# Hexagonal_MCU_V02.net
KiCad netlist of a schematic drawn in EAGLE
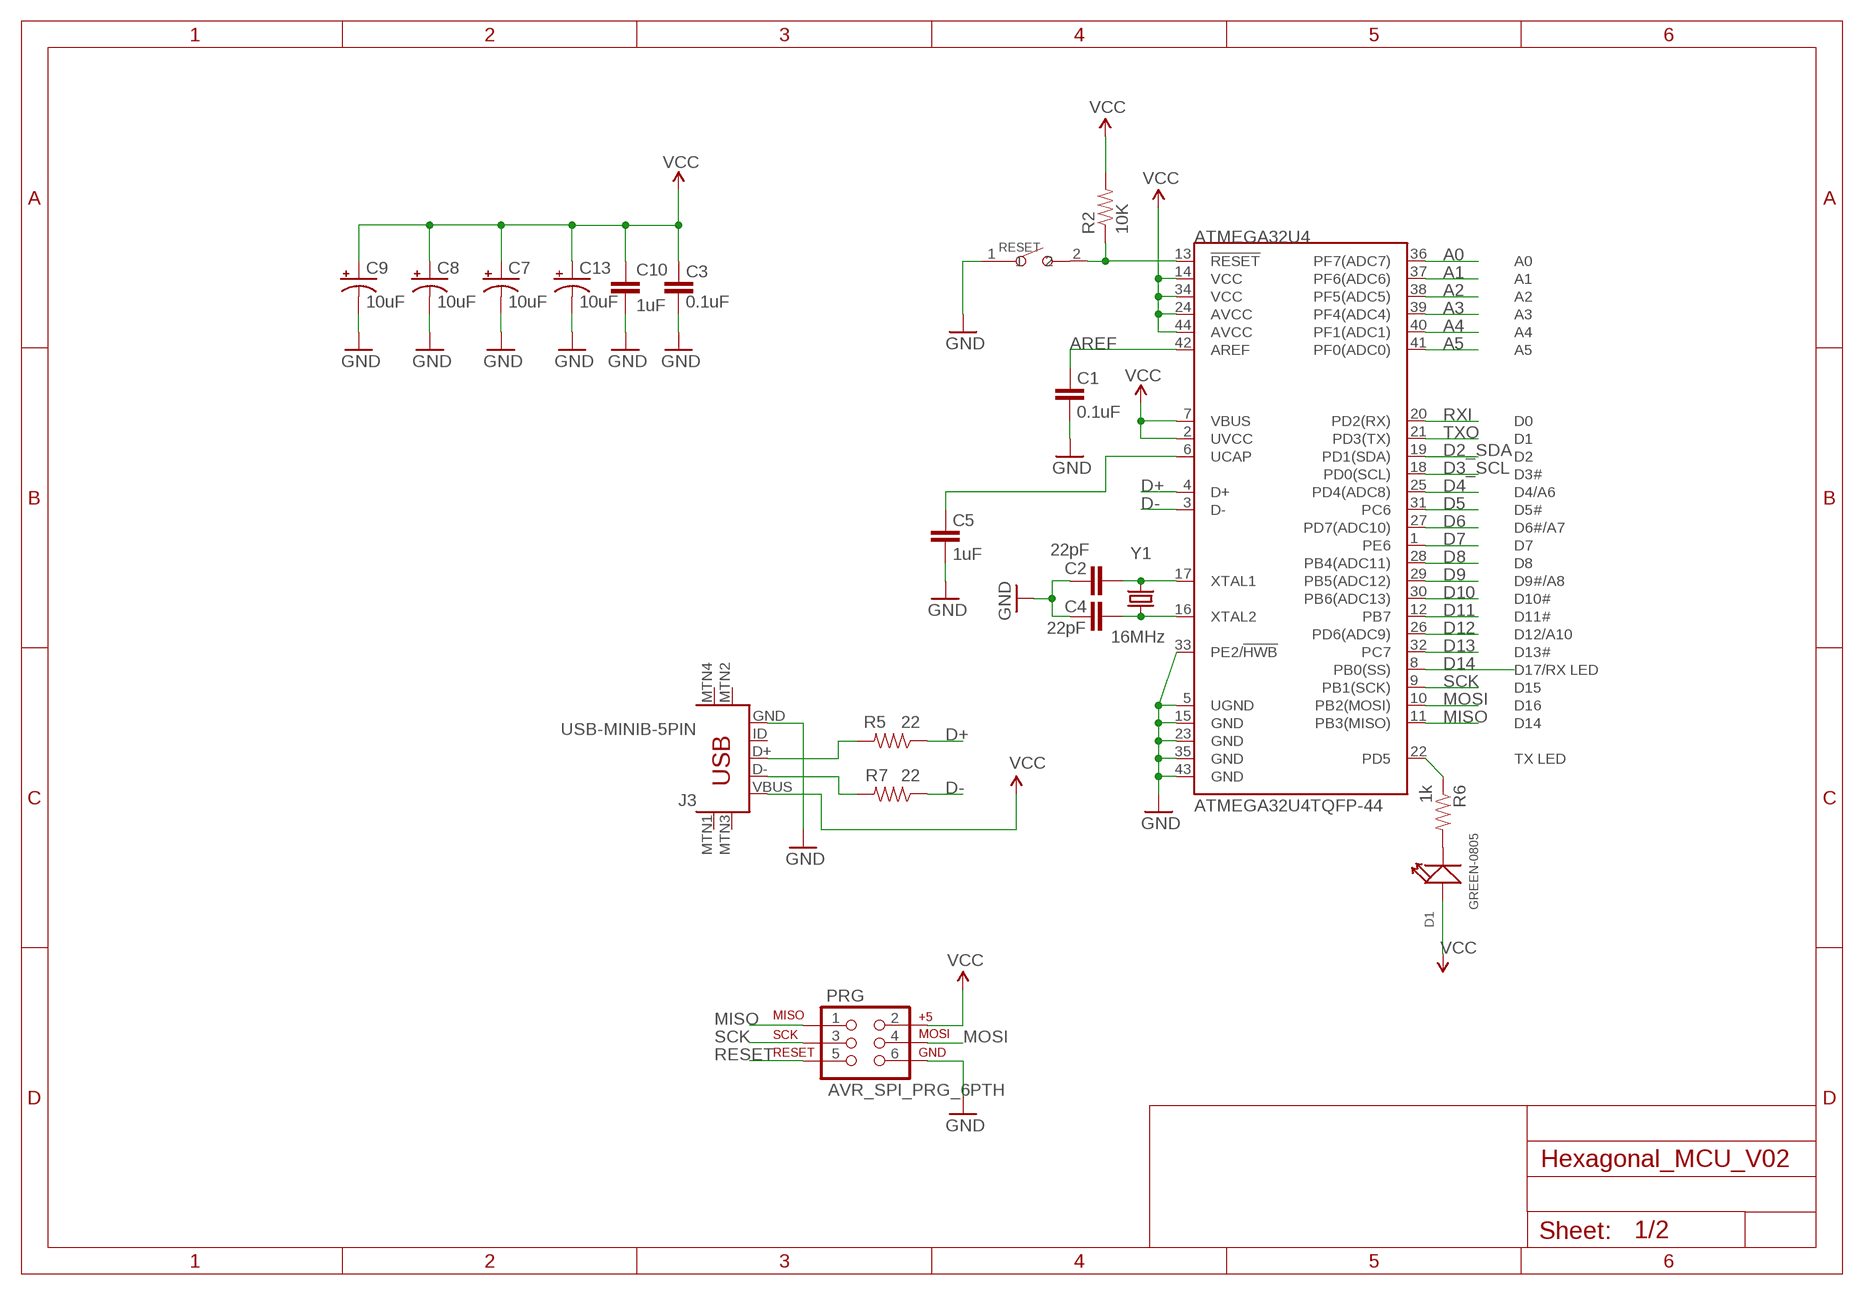
[diagram p0: schematic, sheet 1]
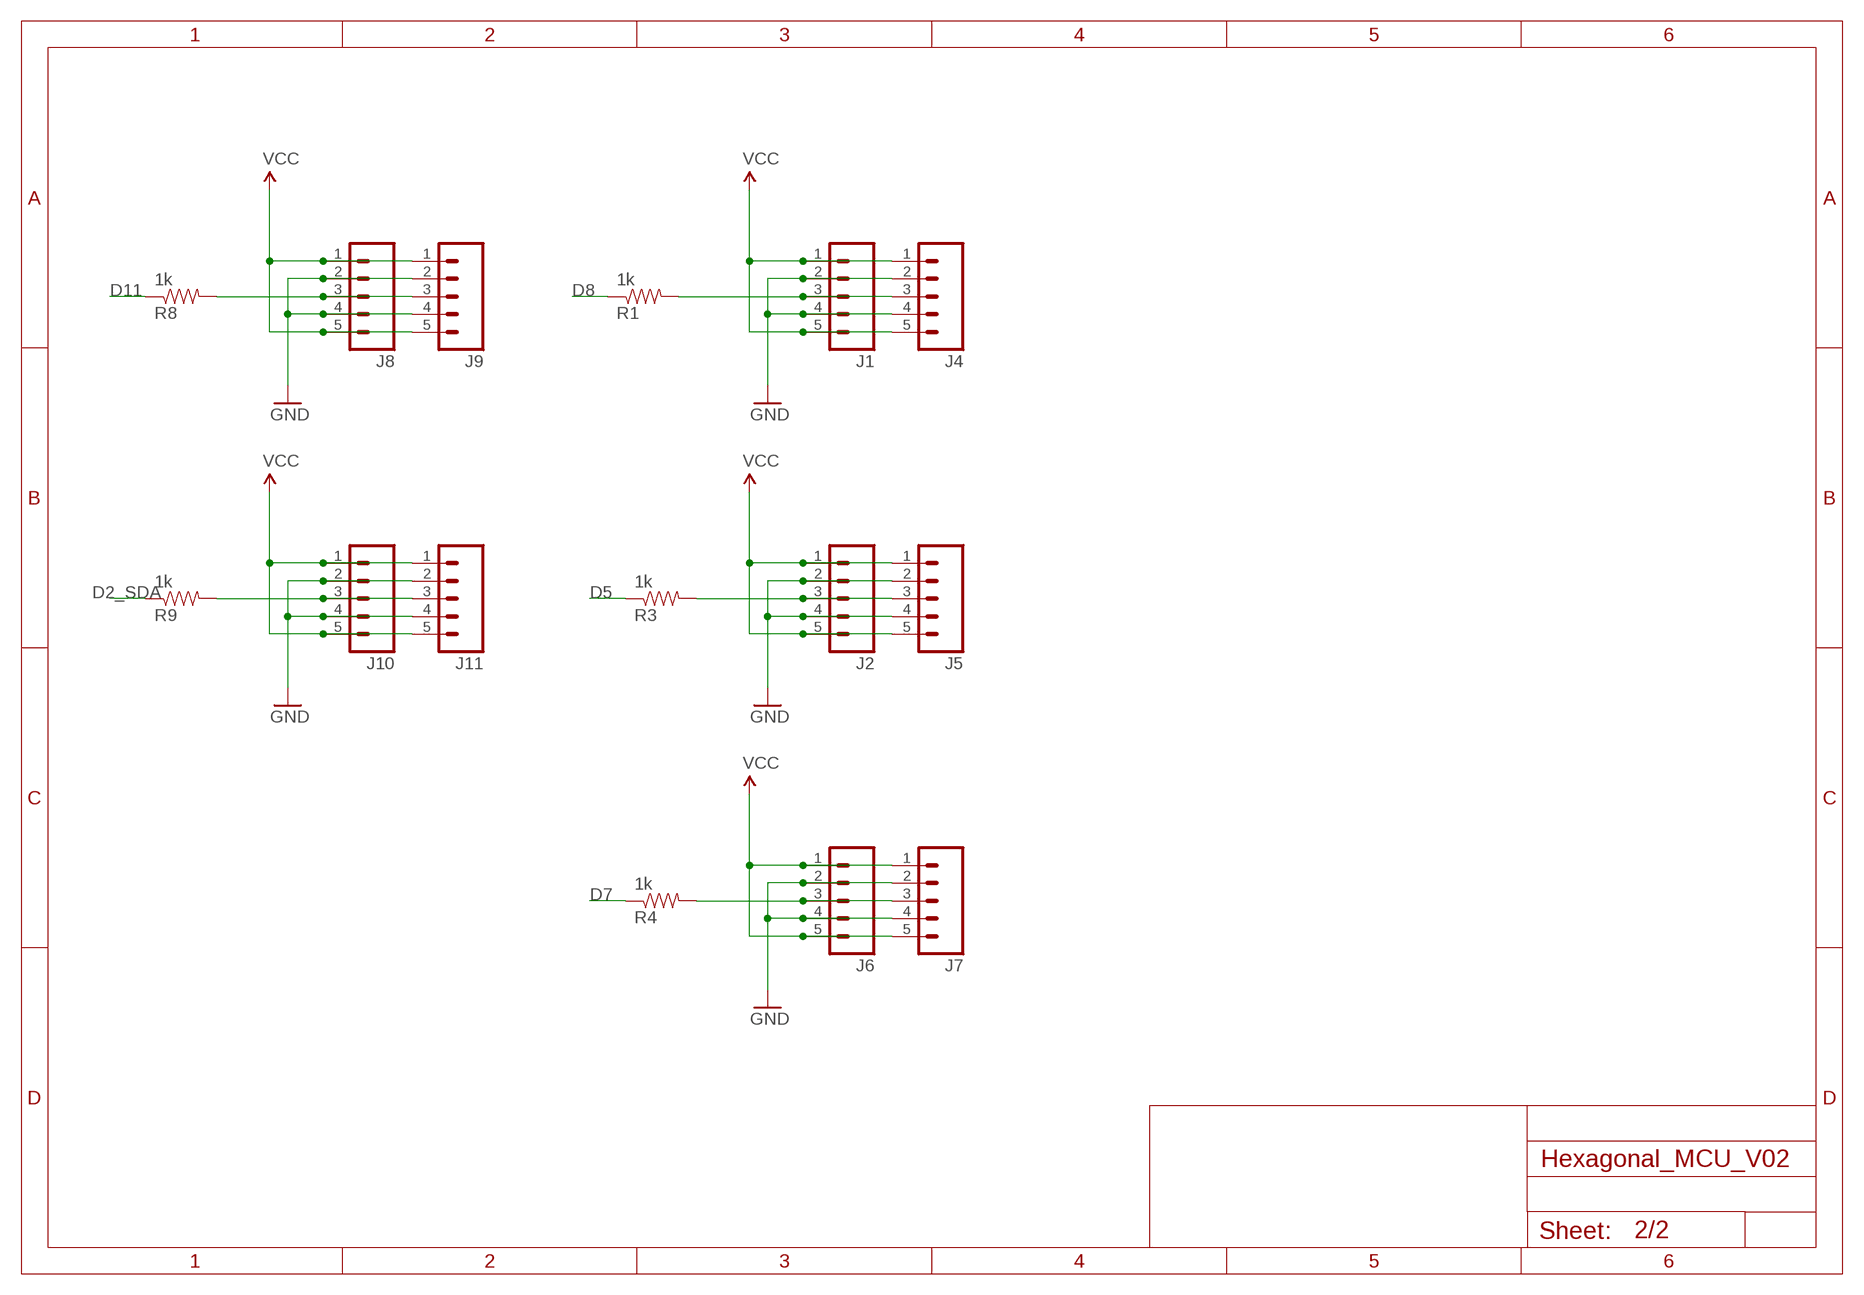
[diagram p1: schematic, sheet 2]

(export (version "E")
  (design (tool "Eeschema 10.0.6"))
  (components
    (comp (ref "ATMEGA32U4")
      (value "ATMEGA32U4TQFP-44")
      (footprint "eagle-import:TQFP44")
      (libsource (lib "eagle-import") (part "ATMEGA32U4TQFP-44"))
    )
    (comp (ref "C1")
      (value "0.1uF")
      (footprint "eagle-import:0805")
      (libsource (lib "eagle-import") (part "CAP0805"))
    )
    (comp (ref "C2")
      (value "22pF")
      (footprint "eagle-import:0805")
      (libsource (lib "eagle-import") (part "CAP0805"))
    )
    (comp (ref "C3")
      (value "0.1uF")
      (footprint "eagle-import:0805")
      (libsource (lib "eagle-import") (part "CAP0805"))
    )
    (comp (ref "C4")
      (value "22pF")
      (footprint "eagle-import:0805")
      (libsource (lib "eagle-import") (part "CAP0805"))
    )
    (comp (ref "C5")
      (value "1uF")
      (footprint "eagle-import:0805")
      (libsource (lib "eagle-import") (part "CAP0805"))
    )
    (comp (ref "C7")
      (value "10uF")
      (footprint "eagle-import:EIA3216")
      (libsource (lib "eagle-import") (part "CAP_POL1206"))
    )
    (comp (ref "C8")
      (value "10uF")
      (footprint "eagle-import:EIA3216")
      (libsource (lib "eagle-import") (part "CAP_POL1206"))
    )
    (comp (ref "C9")
      (value "10uF")
      (footprint "eagle-import:EIA3216")
      (libsource (lib "eagle-import") (part "CAP_POL1206"))
    )
    (comp (ref "C10")
      (value "1uF")
      (footprint "eagle-import:0805")
      (libsource (lib "eagle-import") (part "CAP0805"))
    )
    (comp (ref "C13")
      (value "10uF")
      (footprint "eagle-import:EIA3216")
      (libsource (lib "eagle-import") (part "CAP_POL1206"))
    )
    (comp (ref "D1")
      (value "GREEN-0805")
      (footprint "eagle-import:LED-0805")
      (fields (field (name "MPN") "17-215SYGC/S530-E2/TR8"))
      (libsource (lib "eagle-import") (part "SMD-LED-CLEAR-GREEN(0805)"))
    )
    (comp (ref "J3")
      (value "USB-MINIB-5PIN")
      (footprint "eagle-import:USB-MINIB")
      (libsource (lib "eagle-import") (part "USB-MINIB-5PIN"))
    )
    (comp (ref "PRG")
      (value "AVR_SPI_PRG_6PTH")
      (footprint "eagle-import:2X3")
      (libsource (lib "eagle-import") (part "AVR_SPI_PRG_6PTH"))
    )
    (comp (ref "R2")
      (value "10K")
      (footprint "eagle-import:0805")
      (libsource (lib "eagle-import") (part "RESISTOR0805-RES"))
    )
    (comp (ref "R5")
      (value "22")
      (footprint "eagle-import:0805")
      (libsource (lib "eagle-import") (part "RESISTOR0805-RES"))
    )
    (comp (ref "R6")
      (value "1k")
      (footprint "eagle-import:0805")
      (libsource (lib "eagle-import") (part "RESISTOR0805-RES"))
    )
    (comp (ref "R7")
      (value "22")
      (footprint "eagle-import:0805")
      (libsource (lib "eagle-import") (part "RESISTOR0805-RES"))
    )
    (comp (ref "RESET")
      (value "B3U-1000P-2P-SMD")
      (footprint "eagle-import:SW2-4.0X3.0X2.0")
      (libsource (lib "eagle-import") (part "SMD-BUTTON(2P-4.0X3.0X1.5+0.5MM)SW-TS-017A-2P"))
    )
    (comp (ref "Y1")
      (value "16MHz")
      (footprint "eagle-import:HC49US")
      (libsource (lib "eagle-import") (part "CRYSTALHC49US"))
    )
    (comp (ref "J1")
      (value "M05NO_SILK")
      (footprint "eagle-import:1X05_NO_SILK")
      (libsource (lib "eagle-import") (part "M05NO_SILK"))
    )
    (comp (ref "J2")
      (value "M05NO_SILK")
      (footprint "eagle-import:1X05_NO_SILK")
      (libsource (lib "eagle-import") (part "M05NO_SILK"))
    )
    (comp (ref "J4")
      (value "M05PTH_LONGPADS")
      (footprint "eagle-import:1X05_LONGPADS")
      (libsource (lib "eagle-import") (part "M05PTH_LONGPADS"))
    )
    (comp (ref "J5")
      (value "M05PTH_LONGPADS")
      (footprint "eagle-import:1X05_LONGPADS")
      (libsource (lib "eagle-import") (part "M05PTH_LONGPADS"))
    )
    (comp (ref "J6")
      (value "M05NO_SILK")
      (footprint "eagle-import:1X05_NO_SILK")
      (libsource (lib "eagle-import") (part "M05NO_SILK"))
    )
    (comp (ref "J7")
      (value "M05PTH_LONGPADS")
      (footprint "eagle-import:1X05_LONGPADS")
      (libsource (lib "eagle-import") (part "M05PTH_LONGPADS"))
    )
    (comp (ref "J8")
      (value "M05NO_SILK")
      (footprint "eagle-import:1X05_NO_SILK")
      (libsource (lib "eagle-import") (part "M05NO_SILK"))
    )
    (comp (ref "J9")
      (value "M05PTH_LONGPADS")
      (footprint "eagle-import:1X05_LONGPADS")
      (libsource (lib "eagle-import") (part "M05PTH_LONGPADS"))
    )
    (comp (ref "J10")
      (value "M05NO_SILK")
      (footprint "eagle-import:1X05_NO_SILK")
      (libsource (lib "eagle-import") (part "M05NO_SILK"))
    )
    (comp (ref "J11")
      (value "M05PTH_LONGPADS")
      (footprint "eagle-import:1X05_LONGPADS")
      (libsource (lib "eagle-import") (part "M05PTH_LONGPADS"))
    )
    (comp (ref "R1")
      (value "1k")
      (footprint "eagle-import:0805")
      (libsource (lib "eagle-import") (part "RESISTOR0805-RES"))
    )
    (comp (ref "R3")
      (value "1k")
      (footprint "eagle-import:0805")
      (libsource (lib "eagle-import") (part "RESISTOR0805-RES"))
    )
    (comp (ref "R4")
      (value "1k")
      (footprint "eagle-import:0805")
      (libsource (lib "eagle-import") (part "RESISTOR0805-RES"))
    )
    (comp (ref "R8")
      (value "1k")
      (footprint "eagle-import:0805")
      (libsource (lib "eagle-import") (part "RESISTOR0805-RES"))
    )
    (comp (ref "R9")
      (value "1k")
      (footprint "eagle-import:0805")
      (libsource (lib "eagle-import") (part "RESISTOR0805-RES"))
    )
  )
  (nets
    (net (code "1") (name "5V") (class "Default")
      (node (ref "ATMEGA32U4") (pin "14") (pinfunction "VCC_14") (pintype "bidirectional"))
      (node (ref "ATMEGA32U4") (pin "2") (pinfunction "UVCC_2") (pintype "bidirectional"))
      (node (ref "ATMEGA32U4") (pin "24") (pinfunction "AVCC_24") (pintype "bidirectional"))
      (node (ref "ATMEGA32U4") (pin "34") (pinfunction "VCC_34") (pintype "bidirectional"))
      (node (ref "ATMEGA32U4") (pin "44") (pinfunction "AVCC_44") (pintype "bidirectional"))
      (node (ref "ATMEGA32U4") (pin "7") (pinfunction "VBUS_7") (pintype "bidirectional"))
      (node (ref "C10") (pin "1") (pinfunction "1_1") (pintype "passive"))
      (node (ref "C13") (pin "A") (pinfunction "+_A") (pintype "passive"))
      (node (ref "C3") (pin "2") (pinfunction "2_2") (pintype "passive"))
      (node (ref "C7") (pin "A") (pinfunction "+_A") (pintype "passive"))
      (node (ref "C8") (pin "A") (pinfunction "+_A") (pintype "passive"))
      (node (ref "C9") (pin "A") (pinfunction "+_A") (pintype "passive"))
      (node (ref "D1") (pin "+") (pinfunction "+_+") (pintype "passive"))
      (node (ref "J1") (pin "1") (pinfunction "1_1") (pintype "passive"))
      (node (ref "J1") (pin "5") (pinfunction "5_5") (pintype "passive"))
      (node (ref "J10") (pin "1") (pinfunction "1_1") (pintype "passive"))
      (node (ref "J10") (pin "5") (pinfunction "5_5") (pintype "passive"))
      (node (ref "J11") (pin "1") (pinfunction "1_1") (pintype "passive"))
      (node (ref "J11") (pin "5") (pinfunction "5_5") (pintype "passive"))
      (node (ref "J2") (pin "1") (pinfunction "1_1") (pintype "passive"))
      (node (ref "J2") (pin "5") (pinfunction "5_5") (pintype "passive"))
      (node (ref "J3") (pin "VBUS") (pinfunction "VBUS_VBUS") (pintype "bidirectional"))
      (node (ref "J4") (pin "1") (pinfunction "1_1") (pintype "passive"))
      (node (ref "J4") (pin "5") (pinfunction "5_5") (pintype "passive"))
      (node (ref "J5") (pin "1") (pinfunction "1_1") (pintype "passive"))
      (node (ref "J5") (pin "5") (pinfunction "5_5") (pintype "passive"))
      (node (ref "J6") (pin "1") (pinfunction "1_1") (pintype "passive"))
      (node (ref "J6") (pin "5") (pinfunction "5_5") (pintype "passive"))
      (node (ref "J7") (pin "1") (pinfunction "1_1") (pintype "passive"))
      (node (ref "J7") (pin "5") (pinfunction "5_5") (pintype "passive"))
      (node (ref "J8") (pin "1") (pinfunction "1_1") (pintype "passive"))
      (node (ref "J8") (pin "5") (pinfunction "5_5") (pintype "passive"))
      (node (ref "J9") (pin "1") (pinfunction "1_1") (pintype "passive"))
      (node (ref "J9") (pin "5") (pinfunction "5_5") (pintype "passive"))
      (node (ref "PRG") (pin "2") (pinfunction "2_2") (pintype "passive"))
      (node (ref "R2") (pin "2") (pinfunction "2_2") (pintype "passive"))
    )
    (net (code "2") (name "A0") (class "Default")
      (node (ref "ATMEGA32U4") (pin "36") (pinfunction "PF7(ADC7)_36") (pintype "bidirectional"))
    )
    (net (code "3") (name "A1") (class "Default")
      (node (ref "ATMEGA32U4") (pin "37") (pinfunction "PF6(ADC6)_37") (pintype "bidirectional"))
    )
    (net (code "4") (name "A2") (class "Default")
      (node (ref "ATMEGA32U4") (pin "38") (pinfunction "PF5(ADC5)_38") (pintype "bidirectional"))
    )
    (net (code "5") (name "A3") (class "Default")
      (node (ref "ATMEGA32U4") (pin "39") (pinfunction "PF4(ADC4)_39") (pintype "bidirectional"))
    )
    (net (code "6") (name "A4") (class "Default")
      (node (ref "ATMEGA32U4") (pin "40") (pinfunction "PF1(ADC1)_40") (pintype "bidirectional"))
    )
    (net (code "7") (name "A5") (class "Default")
      (node (ref "ATMEGA32U4") (pin "41") (pinfunction "PF0(ADC0)_41") (pintype "bidirectional"))
    )
    (net (code "8") (name "AREF") (class "Default")
      (node (ref "ATMEGA32U4") (pin "42") (pinfunction "AREF_42") (pintype "bidirectional"))
      (node (ref "C1") (pin "2") (pinfunction "2_2") (pintype "passive"))
    )
    (net (code "9") (name "D+") (class "Default")
      (node (ref "ATMEGA32U4") (pin "4") (pinfunction "D+_4") (pintype "bidirectional"))
      (node (ref "R5") (pin "1") (pinfunction "1_1") (pintype "passive"))
    )
    (net (code "10") (name "D-") (class "Default")
      (node (ref "ATMEGA32U4") (pin "3") (pinfunction "D-_3") (pintype "bidirectional"))
      (node (ref "R7") (pin "1") (pinfunction "1_1") (pintype "passive"))
    )
    (net (code "11") (name "D2_SDA") (class "Default")
      (node (ref "ATMEGA32U4") (pin "19") (pinfunction "PD1(SDA)_19") (pintype "bidirectional"))
      (node (ref "R9") (pin "1") (pinfunction "1_1") (pintype "passive"))
    )
    (net (code "12") (name "D3_SCL") (class "Default")
      (node (ref "ATMEGA32U4") (pin "18") (pinfunction "PD0(SCL)_18") (pintype "bidirectional"))
    )
    (net (code "13") (name "D4") (class "Default")
      (node (ref "ATMEGA32U4") (pin "25") (pinfunction "PD4(ADC8)_25") (pintype "bidirectional"))
    )
    (net (code "14") (name "D5") (class "Default")
      (node (ref "ATMEGA32U4") (pin "31") (pinfunction "PC6_31") (pintype "bidirectional"))
      (node (ref "R3") (pin "1") (pinfunction "1_1") (pintype "passive"))
    )
    (net (code "15") (name "D6") (class "Default")
      (node (ref "ATMEGA32U4") (pin "27") (pinfunction "PD7(ADC10)_27") (pintype "bidirectional"))
    )
    (net (code "16") (name "D7") (class "Default")
      (node (ref "ATMEGA32U4") (pin "1") (pinfunction "PE6_1") (pintype "bidirectional"))
      (node (ref "R4") (pin "1") (pinfunction "1_1") (pintype "passive"))
    )
    (net (code "17") (name "D8") (class "Default")
      (node (ref "ATMEGA32U4") (pin "28") (pinfunction "PB4(ADC11)_28") (pintype "bidirectional"))
      (node (ref "R1") (pin "1") (pinfunction "1_1") (pintype "passive"))
    )
    (net (code "18") (name "D9") (class "Default")
      (node (ref "ATMEGA32U4") (pin "29") (pinfunction "PB5(ADC12)_29") (pintype "bidirectional"))
    )
    (net (code "19") (name "D10") (class "Default")
      (node (ref "ATMEGA32U4") (pin "30") (pinfunction "PB6(ADC13)_30") (pintype "bidirectional"))
    )
    (net (code "20") (name "D11") (class "Default")
      (node (ref "ATMEGA32U4") (pin "12") (pinfunction "PB7_12") (pintype "bidirectional"))
      (node (ref "R8") (pin "1") (pinfunction "1_1") (pintype "passive"))
    )
    (net (code "21") (name "D12") (class "Default")
      (node (ref "ATMEGA32U4") (pin "26") (pinfunction "PD6(ADC9)_26") (pintype "bidirectional"))
    )
    (net (code "22") (name "D13") (class "Default")
      (node (ref "ATMEGA32U4") (pin "32") (pinfunction "PC7_32") (pintype "bidirectional"))
    )
    (net (code "23") (name "D14") (class "Default")
      (node (ref "ATMEGA32U4") (pin "8") (pinfunction "PB0(SS)_8") (pintype "bidirectional"))
    )
    (net (code "24") (name "GND") (class "Default")
      (node (ref "ATMEGA32U4") (pin "15") (pinfunction "GND_15") (pintype "bidirectional"))
      (node (ref "ATMEGA32U4") (pin "23") (pinfunction "GND_23") (pintype "bidirectional"))
      (node (ref "ATMEGA32U4") (pin "33") (pinfunction "PE2/~{HWB}_33") (pintype "bidirectional"))
      (node (ref "ATMEGA32U4") (pin "35") (pinfunction "GND_35") (pintype "bidirectional"))
      (node (ref "ATMEGA32U4") (pin "43") (pinfunction "GND_43") (pintype "bidirectional"))
      (node (ref "ATMEGA32U4") (pin "5") (pinfunction "UGND_5") (pintype "bidirectional"))
      (node (ref "C1") (pin "1") (pinfunction "1_1") (pintype "passive"))
      (node (ref "C10") (pin "2") (pinfunction "2_2") (pintype "passive"))
      (node (ref "C13") (pin "C") (pinfunction "-_C") (pintype "passive"))
      (node (ref "C2") (pin "2") (pinfunction "2_2") (pintype "passive"))
      (node (ref "C3") (pin "1") (pinfunction "1_1") (pintype "passive"))
      (node (ref "C4") (pin "2") (pinfunction "2_2") (pintype "passive"))
      (node (ref "C5") (pin "1") (pinfunction "1_1") (pintype "passive"))
      (node (ref "C7") (pin "C") (pinfunction "-_C") (pintype "passive"))
      (node (ref "C8") (pin "C") (pinfunction "-_C") (pintype "passive"))
      (node (ref "C9") (pin "C") (pinfunction "-_C") (pintype "passive"))
      (node (ref "J1") (pin "2") (pinfunction "2_2") (pintype "passive"))
      (node (ref "J1") (pin "4") (pinfunction "4_4") (pintype "passive"))
      (node (ref "J10") (pin "2") (pinfunction "2_2") (pintype "passive"))
      (node (ref "J10") (pin "4") (pinfunction "4_4") (pintype "passive"))
      (node (ref "J11") (pin "2") (pinfunction "2_2") (pintype "passive"))
      (node (ref "J11") (pin "4") (pinfunction "4_4") (pintype "passive"))
      (node (ref "J2") (pin "2") (pinfunction "2_2") (pintype "passive"))
      (node (ref "J2") (pin "4") (pinfunction "4_4") (pintype "passive"))
      (node (ref "J3") (pin "GND") (pinfunction "GND_GND") (pintype "bidirectional"))
      (node (ref "J4") (pin "2") (pinfunction "2_2") (pintype "passive"))
      (node (ref "J4") (pin "4") (pinfunction "4_4") (pintype "passive"))
      (node (ref "J5") (pin "2") (pinfunction "2_2") (pintype "passive"))
      (node (ref "J5") (pin "4") (pinfunction "4_4") (pintype "passive"))
      (node (ref "J6") (pin "2") (pinfunction "2_2") (pintype "passive"))
      (node (ref "J6") (pin "4") (pinfunction "4_4") (pintype "passive"))
      (node (ref "J7") (pin "2") (pinfunction "2_2") (pintype "passive"))
      (node (ref "J7") (pin "4") (pinfunction "4_4") (pintype "passive"))
      (node (ref "J8") (pin "2") (pinfunction "2_2") (pintype "passive"))
      (node (ref "J8") (pin "4") (pinfunction "4_4") (pintype "passive"))
      (node (ref "J9") (pin "2") (pinfunction "2_2") (pintype "passive"))
      (node (ref "J9") (pin "4") (pinfunction "4_4") (pintype "passive"))
      (node (ref "PRG") (pin "6") (pinfunction "6_6") (pintype "passive"))
      (node (ref "RESET") (pin "1") (pinfunction "1_1") (pintype "bidirectional"))
    )
    (net (code "25") (name "MISO") (class "Default")
      (node (ref "ATMEGA32U4") (pin "11") (pinfunction "PB3(MISO)_11") (pintype "bidirectional"))
      (node (ref "PRG") (pin "1") (pinfunction "1_1") (pintype "passive"))
    )
    (net (code "26") (name "MOSI") (class "Default")
      (node (ref "ATMEGA32U4") (pin "10") (pinfunction "PB2(MOSI)_10") (pintype "bidirectional"))
      (node (ref "PRG") (pin "4") (pinfunction "4_4") (pintype "passive"))
    )
    (net (code "27") (name "Net-(ATMEGA32U4-PD5)") (class "Default")
      (node (ref "ATMEGA32U4") (pin "22") (pinfunction "PD5_22") (pintype "bidirectional"))
      (node (ref "R6") (pin "1") (pinfunction "1_1") (pintype "passive"))
    )
    (net (code "28") (name "Net-(ATMEGA32U4-UCAP)") (class "Default")
      (node (ref "ATMEGA32U4") (pin "6") (pinfunction "UCAP_6") (pintype "bidirectional"))
      (node (ref "C5") (pin "2") (pinfunction "2_2") (pintype "passive"))
    )
    (net (code "29") (name "Net-(ATMEGA32U4-XTAL1)") (class "Default")
      (node (ref "ATMEGA32U4") (pin "17") (pinfunction "XTAL1_17") (pintype "bidirectional"))
      (node (ref "C2") (pin "1") (pinfunction "1_1") (pintype "passive"))
      (node (ref "Y1") (pin "2") (pinfunction "2_2") (pintype "passive"))
    )
    (net (code "30") (name "Net-(ATMEGA32U4-XTAL2)") (class "Default")
      (node (ref "ATMEGA32U4") (pin "16") (pinfunction "XTAL2_16") (pintype "bidirectional"))
      (node (ref "C4") (pin "1") (pinfunction "1_1") (pintype "passive"))
      (node (ref "Y1") (pin "1") (pinfunction "1_1") (pintype "passive"))
    )
    (net (code "31") (name "Net-(D1-Pad-)") (class "Default")
      (node (ref "D1") (pin "-") (pinfunction "-_-") (pintype "passive"))
      (node (ref "R6") (pin "2") (pinfunction "2_2") (pintype "passive"))
    )
    (net (code "32") (name "Net-(J1-Pad3)") (class "Default")
      (node (ref "J1") (pin "3") (pinfunction "3_3") (pintype "passive"))
      (node (ref "J4") (pin "3") (pinfunction "3_3") (pintype "passive"))
      (node (ref "R1") (pin "2") (pinfunction "2_2") (pintype "passive"))
    )
    (net (code "33") (name "Net-(J2-Pad3)") (class "Default")
      (node (ref "J2") (pin "3") (pinfunction "3_3") (pintype "passive"))
      (node (ref "J5") (pin "3") (pinfunction "3_3") (pintype "passive"))
      (node (ref "R3") (pin "2") (pinfunction "2_2") (pintype "passive"))
    )
    (net (code "34") (name "Net-(J3-PadD+)") (class "Default")
      (node (ref "J3") (pin "D+") (pinfunction "D+_D+") (pintype "bidirectional"))
      (node (ref "R5") (pin "2") (pinfunction "2_2") (pintype "passive"))
    )
    (net (code "35") (name "Net-(J3-PadD-)") (class "Default")
      (node (ref "J3") (pin "D-") (pinfunction "D-_D-") (pintype "bidirectional"))
      (node (ref "R7") (pin "2") (pinfunction "2_2") (pintype "passive"))
    )
    (net (code "36") (name "Net-(J6-Pad3)") (class "Default")
      (node (ref "J6") (pin "3") (pinfunction "3_3") (pintype "passive"))
      (node (ref "J7") (pin "3") (pinfunction "3_3") (pintype "passive"))
      (node (ref "R4") (pin "2") (pinfunction "2_2") (pintype "passive"))
    )
    (net (code "37") (name "Net-(J8-Pad3)") (class "Default")
      (node (ref "J8") (pin "3") (pinfunction "3_3") (pintype "passive"))
      (node (ref "J9") (pin "3") (pinfunction "3_3") (pintype "passive"))
      (node (ref "R8") (pin "2") (pinfunction "2_2") (pintype "passive"))
    )
    (net (code "38") (name "Net-(J10-Pad3)") (class "Default")
      (node (ref "J10") (pin "3") (pinfunction "3_3") (pintype "passive"))
      (node (ref "J11") (pin "3") (pinfunction "3_3") (pintype "passive"))
      (node (ref "R9") (pin "2") (pinfunction "2_2") (pintype "passive"))
    )
    (net (code "39") (name "RESET") (class "Default")
      (node (ref "ATMEGA32U4") (pin "13") (pinfunction "~{RESET}_13") (pintype "bidirectional"))
      (node (ref "PRG") (pin "5") (pinfunction "5_5") (pintype "passive"))
      (node (ref "R2") (pin "1") (pinfunction "1_1") (pintype "passive"))
      (node (ref "RESET") (pin "2") (pinfunction "2_2") (pintype "bidirectional"))
    )
    (net (code "40") (name "RXI") (class "Default")
      (node (ref "ATMEGA32U4") (pin "20") (pinfunction "PD2(RX)_20") (pintype "bidirectional"))
    )
    (net (code "41") (name "SCK") (class "Default")
      (node (ref "ATMEGA32U4") (pin "9") (pinfunction "PB1(SCK)_9") (pintype "bidirectional"))
      (node (ref "PRG") (pin "3") (pinfunction "3_3") (pintype "passive"))
    )
    (net (code "42") (name "TXO") (class "Default")
      (node (ref "ATMEGA32U4") (pin "21") (pinfunction "PD3(TX)_21") (pintype "bidirectional"))
    )
    (net (code "43") (name "unconnected-(J3-MTN1-PadMTN3)") (class "Default")
      (node (ref "J3") (pin "MTN3") (pinfunction "MTN1_MTN3") (pintype "bidirectional"))
    )
    (net (code "44") (name "unconnected-(J3-MTN2-PadMTN1)") (class "Default")
      (node (ref "J3") (pin "MTN1") (pinfunction "MTN2_MTN1") (pintype "bidirectional"))
    )
    (net (code "45") (name "unconnected-(J3-MTN3-PadMTN2)") (class "Default")
      (node (ref "J3") (pin "MTN2") (pinfunction "MTN3_MTN2") (pintype "bidirectional"))
    )
    (net (code "46") (name "unconnected-(J3-PadID)") (class "Default")
      (node (ref "J3") (pin "ID") (pinfunction "ID_ID") (pintype "bidirectional"))
    )
    (net (code "47") (name "unconnected-(J3-PadMTN4)") (class "Default")
      (node (ref "J3") (pin "MTN4") (pinfunction "MTN4_MTN4") (pintype "bidirectional"))
    )
  )
)
